# LD12.net
KiCad netlist of a schematic drawn in EAGLE
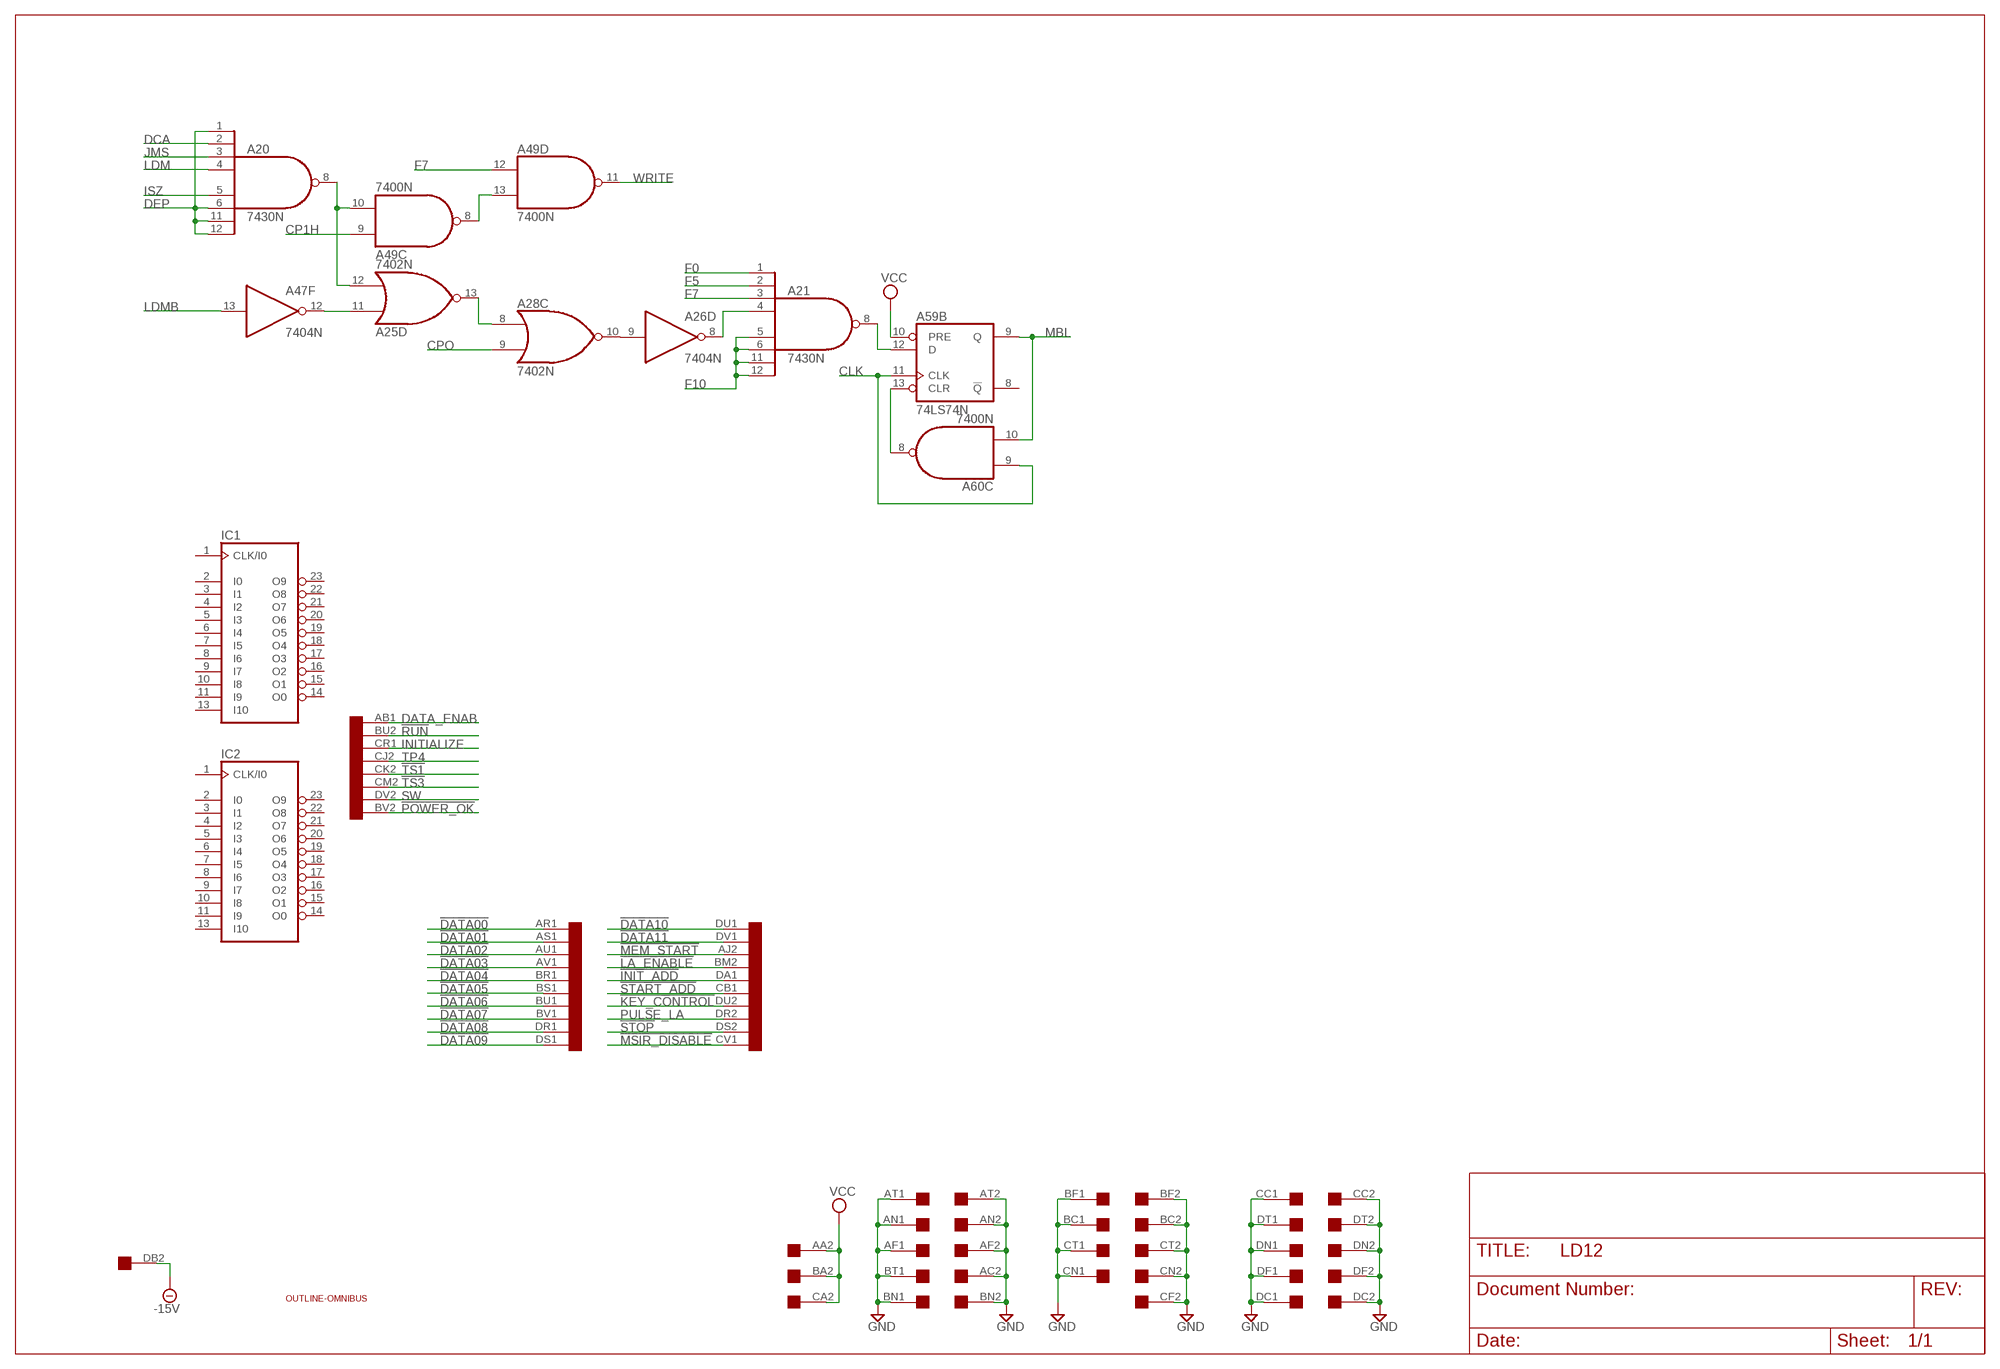
[diagram p0: schematic, sheet 1]

(export (version "E")
  (design (tool "Eeschema 10.0.6"))
  (components
    (comp (ref "A20")
      (value "7430N")
      (footprint "eagle-import:DIL14")
      (libsource (lib "eagle-import") (part "7430N"))
    )
    (comp (ref "A21")
      (value "7430N")
      (footprint "eagle-import:DIL14")
      (libsource (lib "eagle-import") (part "7430N"))
    )
    (comp (ref "A25")
      (value "7402N")
      (footprint "eagle-import:DIL14")
      (libsource (lib "eagle-import") (part "7402N"))
    )
    (comp (ref "A26")
      (value "7404N")
      (footprint "eagle-import:DIL14")
      (libsource (lib "eagle-import") (part "7404N"))
    )
    (comp (ref "A28")
      (value "7402N")
      (footprint "eagle-import:DIL14")
      (libsource (lib "eagle-import") (part "7402N"))
    )
    (comp (ref "A47")
      (value "7404N")
      (footprint "eagle-import:DIL14")
      (libsource (lib "eagle-import") (part "7404N"))
    )
    (comp (ref "A49")
      (value "7400N")
      (footprint "eagle-import:DIL14")
      (libsource (lib "eagle-import") (part "7400N"))
    )
    (comp (ref "A59")
      (value "74LS74N")
      (footprint "eagle-import:DIL14")
      (libsource (lib "eagle-import") (part "7474NLS"))
    )
    (comp (ref "A60")
      (value "7400N")
      (footprint "eagle-import:DIL14")
      (libsource (lib "eagle-import") (part "7400N"))
    )
    (comp (ref "IC1")
      (value "22V10")
      (footprint "eagle-import:DIL24-3")
      (fields (field (name "MPN") "GAL22V10D-7LPN"))
      (libsource (lib "eagle-import") (part "22V10"))
    )
    (comp (ref "IC2")
      (value "22V10")
      (footprint "eagle-import:DIL24-3")
      (fields (field (name "MPN") "GAL22V10D-7LPN"))
      (libsource (lib "eagle-import") (part "22V10"))
    )
    (comp (ref "U$1")
      (value "OUTLINE-OMNIBUS")
      (footprint "eagle-import:OMNIBUS")
      (libsource (lib "eagle-import") (part "OUTLINE-OMNIBUS"))
    )
    (comp (ref "U$2")
      (value "QUAD")
      (footprint "eagle-import:EDGE-CON8")
      (libsource (lib "eagle-import") (part "QUAD"))
    )
  )
  (nets
    (net (code "1") (name "-15V") (class "Default")
      (node (ref "U$2") (pin "DB2") (pinfunction "1_DB2") (pintype "bidirectional"))
    )
    (net (code "2") (name "/CLK") (class "Default")
      (node (ref "A59") (pin "11") (pinfunction "CLK_11") (pintype "input"))
      (node (ref "A60") (pin "9") (pinfunction "I0_9") (pintype "input"))
    )
    (net (code "3") (name "/CP1H") (class "Default")
      (node (ref "A49") (pin "9") (pinfunction "I0_9") (pintype "input"))
    )
    (net (code "4") (name "/CPO") (class "Default")
      (node (ref "A28") (pin "9") (pinfunction "I1_9") (pintype "input"))
    )
    (net (code "5") (name "/DATA_ENAB") (class "Default")
      (node (ref "U$2") (pin "AB1") (pinfunction "1_AB1") (pintype "bidirectional"))
    )
    (net (code "6") (name "/DCA") (class "Default")
      (node (ref "A20") (pin "2") (pinfunction "I1_2") (pintype "input"))
    )
    (net (code "7") (name "/DEP") (class "Default")
      (node (ref "A20") (pin "1") (pinfunction "I0_1") (pintype "input"))
      (node (ref "A20") (pin "11") (pinfunction "I6_11") (pintype "input"))
      (node (ref "A20") (pin "12") (pinfunction "I7_12") (pintype "input"))
      (node (ref "A20") (pin "6") (pinfunction "I5_6") (pintype "input"))
    )
    (net (code "8") (name "/F0") (class "Default")
      (node (ref "A21") (pin "1") (pinfunction "I0_1") (pintype "input"))
    )
    (net (code "9") (name "/F5") (class "Default")
      (node (ref "A21") (pin "2") (pinfunction "I1_2") (pintype "input"))
    )
    (net (code "10") (name "/F7") (class "Default")
      (node (ref "A21") (pin "3") (pinfunction "I2_3") (pintype "input"))
      (node (ref "A49") (pin "12") (pinfunction "I0_12") (pintype "input"))
    )
    (net (code "11") (name "/F10") (class "Default")
      (node (ref "A21") (pin "11") (pinfunction "I6_11") (pintype "input"))
      (node (ref "A21") (pin "12") (pinfunction "I7_12") (pintype "input"))
      (node (ref "A21") (pin "5") (pinfunction "I4_5") (pintype "input"))
      (node (ref "A21") (pin "6") (pinfunction "I5_6") (pintype "input"))
    )
    (net (code "12") (name "/INITIALIZE") (class "Default")
      (node (ref "U$2") (pin "CR1") (pinfunction "1_CR1") (pintype "bidirectional"))
    )
    (net (code "13") (name "/ISZ") (class "Default")
      (node (ref "A20") (pin "5") (pinfunction "I4_5") (pintype "input"))
    )
    (net (code "14") (name "/JMS") (class "Default")
      (node (ref "A20") (pin "3") (pinfunction "I2_3") (pintype "input"))
    )
    (net (code "15") (name "/LDM") (class "Default")
      (node (ref "A20") (pin "4") (pinfunction "I3_4") (pintype "input"))
    )
    (net (code "16") (name "/LDMB") (class "Default")
      (node (ref "A47") (pin "13") (pinfunction "I_13") (pintype "input"))
    )
    (net (code "17") (name "/MBL") (class "Default")
      (node (ref "A59") (pin "9") (pinfunction "Q_9") (pintype "output"))
      (node (ref "A60") (pin "10") (pinfunction "I1_10") (pintype "input"))
    )
    (net (code "18") (name "/PULSE_LA") (class "Default")
      (node (ref "U$2") (pin "DR2") (pinfunction "1_DR2") (pintype "bidirectional"))
    )
    (net (code "19") (name "/SW") (class "Default")
      (node (ref "U$2") (pin "DV2") (pinfunction "1_DV2") (pintype "bidirectional"))
    )
    (net (code "20") (name "/TP4") (class "Default")
      (node (ref "U$2") (pin "CJ2") (pinfunction "1_CJ2") (pintype "bidirectional"))
    )
    (net (code "21") (name "/WRITE") (class "Default")
      (node (ref "A49") (pin "11") (pinfunction "O_11") (pintype "output"))
    )
    (net (code "22") (name "/~{DATA00}") (class "Default")
      (node (ref "U$2") (pin "AR1") (pinfunction "1_AR1") (pintype "bidirectional"))
    )
    (net (code "23") (name "/~{DATA01}") (class "Default")
      (node (ref "U$2") (pin "AS1") (pinfunction "1_AS1") (pintype "bidirectional"))
    )
    (net (code "24") (name "/~{DATA02}") (class "Default")
      (node (ref "U$2") (pin "AU1") (pinfunction "1_AU1") (pintype "bidirectional"))
    )
    (net (code "25") (name "/~{DATA03}") (class "Default")
      (node (ref "U$2") (pin "AV1") (pinfunction "1_AV1") (pintype "bidirectional"))
    )
    (net (code "26") (name "/~{DATA04}") (class "Default")
      (node (ref "U$2") (pin "BR1") (pinfunction "1_BR1") (pintype "bidirectional"))
    )
    (net (code "27") (name "/~{DATA05}") (class "Default")
      (node (ref "U$2") (pin "BS1") (pinfunction "1_BS1") (pintype "bidirectional"))
    )
    (net (code "28") (name "/~{DATA06}") (class "Default")
      (node (ref "U$2") (pin "BU1") (pinfunction "1_BU1") (pintype "bidirectional"))
    )
    (net (code "29") (name "/~{DATA07}") (class "Default")
      (node (ref "U$2") (pin "BV1") (pinfunction "1_BV1") (pintype "bidirectional"))
    )
    (net (code "30") (name "/~{DATA08}") (class "Default")
      (node (ref "U$2") (pin "DR1") (pinfunction "1_DR1") (pintype "bidirectional"))
    )
    (net (code "31") (name "/~{DATA09}") (class "Default")
      (node (ref "U$2") (pin "DS1") (pinfunction "1_DS1") (pintype "bidirectional"))
    )
    (net (code "32") (name "/~{DATA10}") (class "Default")
      (node (ref "U$2") (pin "DU1") (pinfunction "1_DU1") (pintype "bidirectional"))
    )
    (net (code "33") (name "/~{DATA11}") (class "Default")
      (node (ref "U$2") (pin "DV1") (pinfunction "1_DV1") (pintype "bidirectional"))
    )
    (net (code "34") (name "/~{INIT_ADD}") (class "Default")
      (node (ref "U$2") (pin "DA1") (pinfunction "1_DA1") (pintype "bidirectional"))
    )
    (net (code "35") (name "/~{KEY_CONTROL}") (class "Default")
      (node (ref "U$2") (pin "DU2") (pinfunction "1_DU2") (pintype "bidirectional"))
    )
    (net (code "36") (name "/~{LA_ENABLE}") (class "Default")
      (node (ref "U$2") (pin "BM2") (pinfunction "1_BM2") (pintype "bidirectional"))
    )
    (net (code "37") (name "/~{MEM_START}") (class "Default")
      (node (ref "U$2") (pin "AJ2") (pinfunction "1_AJ2") (pintype "bidirectional"))
    )
    (net (code "38") (name "/~{MSIR_DISABLE}") (class "Default")
      (node (ref "U$2") (pin "CV1") (pinfunction "1_CV1") (pintype "bidirectional"))
    )
    (net (code "39") (name "/~{POWER_OK}") (class "Default")
      (node (ref "U$2") (pin "BV2") (pinfunction "1_BV2") (pintype "bidirectional"))
    )
    (net (code "40") (name "/~{RUN}") (class "Default")
      (node (ref "U$2") (pin "BU2") (pinfunction "1_BU2") (pintype "bidirectional"))
    )
    (net (code "41") (name "/~{START_ADD}") (class "Default")
      (node (ref "U$2") (pin "CB1") (pinfunction "1_CB1") (pintype "bidirectional"))
    )
    (net (code "42") (name "/~{STOP}") (class "Default")
      (node (ref "U$2") (pin "DS2") (pinfunction "1_DS2") (pintype "bidirectional"))
    )
    (net (code "43") (name "/~{TS1}") (class "Default")
      (node (ref "U$2") (pin "CK2") (pinfunction "1_CK2") (pintype "bidirectional"))
    )
    (net (code "44") (name "/~{TS3}") (class "Default")
      (node (ref "U$2") (pin "CM2") (pinfunction "1_CM2") (pintype "bidirectional"))
    )
    (net (code "45") (name "GND") (class "Default")
      (node (ref "U$2") (pin "AC2") (pinfunction "1_AC2") (pintype "bidirectional"))
      (node (ref "U$2") (pin "AF1") (pinfunction "1_AF1") (pintype "bidirectional"))
      (node (ref "U$2") (pin "AF2") (pinfunction "1_AF2") (pintype "bidirectional"))
      (node (ref "U$2") (pin "AN1") (pinfunction "1_AN1") (pintype "bidirectional"))
      (node (ref "U$2") (pin "AN2") (pinfunction "1_AN2") (pintype "bidirectional"))
      (node (ref "U$2") (pin "AT1") (pinfunction "1_AT1") (pintype "bidirectional"))
      (node (ref "U$2") (pin "AT2") (pinfunction "1_AT2") (pintype "bidirectional"))
      (node (ref "U$2") (pin "BC1") (pinfunction "1_BC1") (pintype "bidirectional"))
      (node (ref "U$2") (pin "BC2") (pinfunction "1_BC2") (pintype "bidirectional"))
      (node (ref "U$2") (pin "BF1") (pinfunction "1_BF1") (pintype "bidirectional"))
      (node (ref "U$2") (pin "BF2") (pinfunction "1_BF2") (pintype "bidirectional"))
      (node (ref "U$2") (pin "BN1") (pinfunction "1_BN1") (pintype "bidirectional"))
      (node (ref "U$2") (pin "BN2") (pinfunction "1_BN2") (pintype "bidirectional"))
      (node (ref "U$2") (pin "BT1") (pinfunction "1_BT1") (pintype "bidirectional"))
      (node (ref "U$2") (pin "CC1") (pinfunction "1_CC1") (pintype "bidirectional"))
      (node (ref "U$2") (pin "CC2") (pinfunction "1_CC2") (pintype "bidirectional"))
      (node (ref "U$2") (pin "CF2") (pinfunction "1_CF2") (pintype "bidirectional"))
      (node (ref "U$2") (pin "CN1") (pinfunction "1_CN1") (pintype "bidirectional"))
      (node (ref "U$2") (pin "CN2") (pinfunction "1_CN2") (pintype "bidirectional"))
      (node (ref "U$2") (pin "CT1") (pinfunction "1_CT1") (pintype "bidirectional"))
      (node (ref "U$2") (pin "CT2") (pinfunction "1_CT2") (pintype "bidirectional"))
      (node (ref "U$2") (pin "DC1") (pinfunction "1_DC1") (pintype "bidirectional"))
      (node (ref "U$2") (pin "DC2") (pinfunction "1_DC2") (pintype "bidirectional"))
      (node (ref "U$2") (pin "DF1") (pinfunction "1_DF1") (pintype "bidirectional"))
      (node (ref "U$2") (pin "DF2") (pinfunction "1_DF2") (pintype "bidirectional"))
      (node (ref "U$2") (pin "DN1") (pinfunction "1_DN1") (pintype "bidirectional"))
      (node (ref "U$2") (pin "DN2") (pinfunction "1_DN2") (pintype "bidirectional"))
      (node (ref "U$2") (pin "DT1") (pinfunction "1_DT1") (pintype "bidirectional"))
      (node (ref "U$2") (pin "DT2") (pinfunction "1_DT2") (pintype "bidirectional"))
    )
    (net (code "46") (name "Net-(A20A-O)") (class "Default")
      (node (ref "A20") (pin "8") (pinfunction "O_8") (pintype "output"))
      (node (ref "A25") (pin "12") (pinfunction "I1_12") (pintype "input"))
      (node (ref "A49") (pin "10") (pinfunction "I1_10") (pintype "input"))
    )
    (net (code "47") (name "Net-(A21A-I3)") (class "Default")
      (node (ref "A21") (pin "4") (pinfunction "I3_4") (pintype "input"))
      (node (ref "A26") (pin "8") (pinfunction "O_8") (pintype "output"))
    )
    (net (code "48") (name "Net-(A21A-O)") (class "Default")
      (node (ref "A21") (pin "8") (pinfunction "O_8") (pintype "output"))
      (node (ref "A59") (pin "12") (pinfunction "D_12") (pintype "input"))
    )
    (net (code "49") (name "Net-(A25D-I0)") (class "Default")
      (node (ref "A25") (pin "11") (pinfunction "I0_11") (pintype "input"))
      (node (ref "A47") (pin "12") (pinfunction "O_12") (pintype "output"))
    )
    (net (code "50") (name "Net-(A25D-O)") (class "Default")
      (node (ref "A25") (pin "13") (pinfunction "O_13") (pintype "output"))
      (node (ref "A28") (pin "8") (pinfunction "I0_8") (pintype "input"))
    )
    (net (code "51") (name "Net-(A26D-I)") (class "Default")
      (node (ref "A26") (pin "9") (pinfunction "I_9") (pintype "input"))
      (node (ref "A28") (pin "10") (pinfunction "O_10") (pintype "output"))
    )
    (net (code "52") (name "Net-(A49C-O)") (class "Default")
      (node (ref "A49") (pin "13") (pinfunction "I1_13") (pintype "input"))
      (node (ref "A49") (pin "8") (pinfunction "O_8") (pintype "output"))
    )
    (net (code "53") (name "Net-(A59B-CLR)") (class "Default")
      (node (ref "A59") (pin "13") (pinfunction "CLR_13") (pintype "input"))
      (node (ref "A60") (pin "8") (pinfunction "O_8") (pintype "output"))
    )
    (net (code "54") (name "VCC") (class "Default")
      (node (ref "A59") (pin "10") (pinfunction "PRE_10") (pintype "input"))
      (node (ref "U$2") (pin "AA2") (pinfunction "1_AA2") (pintype "bidirectional"))
      (node (ref "U$2") (pin "BA2") (pinfunction "1_BA2") (pintype "bidirectional"))
      (node (ref "U$2") (pin "CA2") (pinfunction "1_CA2") (pintype "bidirectional"))
    )
    (net (code "55") (name "unconnected-(A59B-~{Q}-Pad8)") (class "Default")
      (node (ref "A59") (pin "8") (pinfunction "~{Q}_8") (pintype "output"))
    )
    (net (code "56") (name "unconnected-(IC1A-CLK{slash}I0-Pad1)") (class "Default")
      (node (ref "IC1") (pin "1") (pinfunction "CLK/I0_1") (pintype "input"))
    )
    (net (code "57") (name "unconnected-(IC1A-I0-Pad2)") (class "Default")
      (node (ref "IC1") (pin "2") (pinfunction "I0_2") (pintype "input"))
    )
    (net (code "58") (name "unconnected-(IC1A-I1-Pad3)") (class "Default")
      (node (ref "IC1") (pin "3") (pinfunction "I1_3") (pintype "input"))
    )
    (net (code "59") (name "unconnected-(IC1A-I2-Pad4)") (class "Default")
      (node (ref "IC1") (pin "4") (pinfunction "I2_4") (pintype "input"))
    )
    (net (code "60") (name "unconnected-(IC1A-I3-Pad5)") (class "Default")
      (node (ref "IC1") (pin "5") (pinfunction "I3_5") (pintype "input"))
    )
    (net (code "61") (name "unconnected-(IC1A-I4-Pad6)") (class "Default")
      (node (ref "IC1") (pin "6") (pinfunction "I4_6") (pintype "input"))
    )
    (net (code "62") (name "unconnected-(IC1A-I5-Pad7)") (class "Default")
      (node (ref "IC1") (pin "7") (pinfunction "I5_7") (pintype "input"))
    )
    (net (code "63") (name "unconnected-(IC1A-I6-Pad8)") (class "Default")
      (node (ref "IC1") (pin "8") (pinfunction "I6_8") (pintype "input"))
    )
    (net (code "64") (name "unconnected-(IC1A-I7-Pad9)") (class "Default")
      (node (ref "IC1") (pin "9") (pinfunction "I7_9") (pintype "input"))
    )
    (net (code "65") (name "unconnected-(IC1A-I8-Pad10)") (class "Default")
      (node (ref "IC1") (pin "10") (pinfunction "I8_10") (pintype "input"))
    )
    (net (code "66") (name "unconnected-(IC1A-I9-Pad11)") (class "Default")
      (node (ref "IC1") (pin "11") (pinfunction "I9_11") (pintype "input"))
    )
    (net (code "67") (name "unconnected-(IC1A-I10-Pad13)") (class "Default")
      (node (ref "IC1") (pin "13") (pinfunction "I10_13") (pintype "input"))
    )
    (net (code "68") (name "unconnected-(IC1A-O0-Pad14)") (class "Default")
      (node (ref "IC1") (pin "14") (pinfunction "O0_14") (pintype "bidirectional"))
    )
    (net (code "69") (name "unconnected-(IC1A-O1-Pad15)") (class "Default")
      (node (ref "IC1") (pin "15") (pinfunction "O1_15") (pintype "bidirectional"))
    )
    (net (code "70") (name "unconnected-(IC1A-O2-Pad16)") (class "Default")
      (node (ref "IC1") (pin "16") (pinfunction "O2_16") (pintype "bidirectional"))
    )
    (net (code "71") (name "unconnected-(IC1A-O3-Pad17)") (class "Default")
      (node (ref "IC1") (pin "17") (pinfunction "O3_17") (pintype "bidirectional"))
    )
    (net (code "72") (name "unconnected-(IC1A-O4-Pad18)") (class "Default")
      (node (ref "IC1") (pin "18") (pinfunction "O4_18") (pintype "bidirectional"))
    )
    (net (code "73") (name "unconnected-(IC1A-O5-Pad19)") (class "Default")
      (node (ref "IC1") (pin "19") (pinfunction "O5_19") (pintype "bidirectional"))
    )
    (net (code "74") (name "unconnected-(IC1A-O6-Pad20)") (class "Default")
      (node (ref "IC1") (pin "20") (pinfunction "O6_20") (pintype "bidirectional"))
    )
    (net (code "75") (name "unconnected-(IC1A-O7-Pad21)") (class "Default")
      (node (ref "IC1") (pin "21") (pinfunction "O7_21") (pintype "bidirectional"))
    )
    (net (code "76") (name "unconnected-(IC1A-O8-Pad22)") (class "Default")
      (node (ref "IC1") (pin "22") (pinfunction "O8_22") (pintype "bidirectional"))
    )
    (net (code "77") (name "unconnected-(IC1A-O9-Pad23)") (class "Default")
      (node (ref "IC1") (pin "23") (pinfunction "O9_23") (pintype "bidirectional"))
    )
    (net (code "78") (name "unconnected-(IC2A-CLK{slash}I0-Pad1)") (class "Default")
      (node (ref "IC2") (pin "1") (pinfunction "CLK/I0_1") (pintype "input"))
    )
    (net (code "79") (name "unconnected-(IC2A-I0-Pad2)") (class "Default")
      (node (ref "IC2") (pin "2") (pinfunction "I0_2") (pintype "input"))
    )
    (net (code "80") (name "unconnected-(IC2A-I1-Pad3)") (class "Default")
      (node (ref "IC2") (pin "3") (pinfunction "I1_3") (pintype "input"))
    )
    (net (code "81") (name "unconnected-(IC2A-I2-Pad4)") (class "Default")
      (node (ref "IC2") (pin "4") (pinfunction "I2_4") (pintype "input"))
    )
    (net (code "82") (name "unconnected-(IC2A-I3-Pad5)") (class "Default")
      (node (ref "IC2") (pin "5") (pinfunction "I3_5") (pintype "input"))
    )
    (net (code "83") (name "unconnected-(IC2A-I4-Pad6)") (class "Default")
      (node (ref "IC2") (pin "6") (pinfunction "I4_6") (pintype "input"))
    )
    (net (code "84") (name "unconnected-(IC2A-I5-Pad7)") (class "Default")
      (node (ref "IC2") (pin "7") (pinfunction "I5_7") (pintype "input"))
    )
    (net (code "85") (name "unconnected-(IC2A-I6-Pad8)") (class "Default")
      (node (ref "IC2") (pin "8") (pinfunction "I6_8") (pintype "input"))
    )
    (net (code "86") (name "unconnected-(IC2A-I7-Pad9)") (class "Default")
      (node (ref "IC2") (pin "9") (pinfunction "I7_9") (pintype "input"))
    )
    (net (code "87") (name "unconnected-(IC2A-I8-Pad10)") (class "Default")
      (node (ref "IC2") (pin "10") (pinfunction "I8_10") (pintype "input"))
    )
    (net (code "88") (name "unconnected-(IC2A-I9-Pad11)") (class "Default")
      (node (ref "IC2") (pin "11") (pinfunction "I9_11") (pintype "input"))
    )
    (net (code "89") (name "unconnected-(IC2A-I10-Pad13)") (class "Default")
      (node (ref "IC2") (pin "13") (pinfunction "I10_13") (pintype "input"))
    )
    (net (code "90") (name "unconnected-(IC2A-O0-Pad14)") (class "Default")
      (node (ref "IC2") (pin "14") (pinfunction "O0_14") (pintype "bidirectional"))
    )
    (net (code "91") (name "unconnected-(IC2A-O1-Pad15)") (class "Default")
      (node (ref "IC2") (pin "15") (pinfunction "O1_15") (pintype "bidirectional"))
    )
    (net (code "92") (name "unconnected-(IC2A-O2-Pad16)") (class "Default")
      (node (ref "IC2") (pin "16") (pinfunction "O2_16") (pintype "bidirectional"))
    )
    (net (code "93") (name "unconnected-(IC2A-O3-Pad17)") (class "Default")
      (node (ref "IC2") (pin "17") (pinfunction "O3_17") (pintype "bidirectional"))
    )
    (net (code "94") (name "unconnected-(IC2A-O4-Pad18)") (class "Default")
      (node (ref "IC2") (pin "18") (pinfunction "O4_18") (pintype "bidirectional"))
    )
    (net (code "95") (name "unconnected-(IC2A-O5-Pad19)") (class "Default")
      (node (ref "IC2") (pin "19") (pinfunction "O5_19") (pintype "bidirectional"))
    )
    (net (code "96") (name "unconnected-(IC2A-O6-Pad20)") (class "Default")
      (node (ref "IC2") (pin "20") (pinfunction "O6_20") (pintype "bidirectional"))
    )
    (net (code "97") (name "unconnected-(IC2A-O7-Pad21)") (class "Default")
      (node (ref "IC2") (pin "21") (pinfunction "O7_21") (pintype "bidirectional"))
    )
    (net (code "98") (name "unconnected-(IC2A-O8-Pad22)") (class "Default")
      (node (ref "IC2") (pin "22") (pinfunction "O8_22") (pintype "bidirectional"))
    )
    (net (code "99") (name "unconnected-(IC2A-O9-Pad23)") (class "Default")
      (node (ref "IC2") (pin "23") (pinfunction "O9_23") (pintype "bidirectional"))
    )
  )
)
